# Loads.net
KiCad netlist of a schematic drawn in Altium Designer
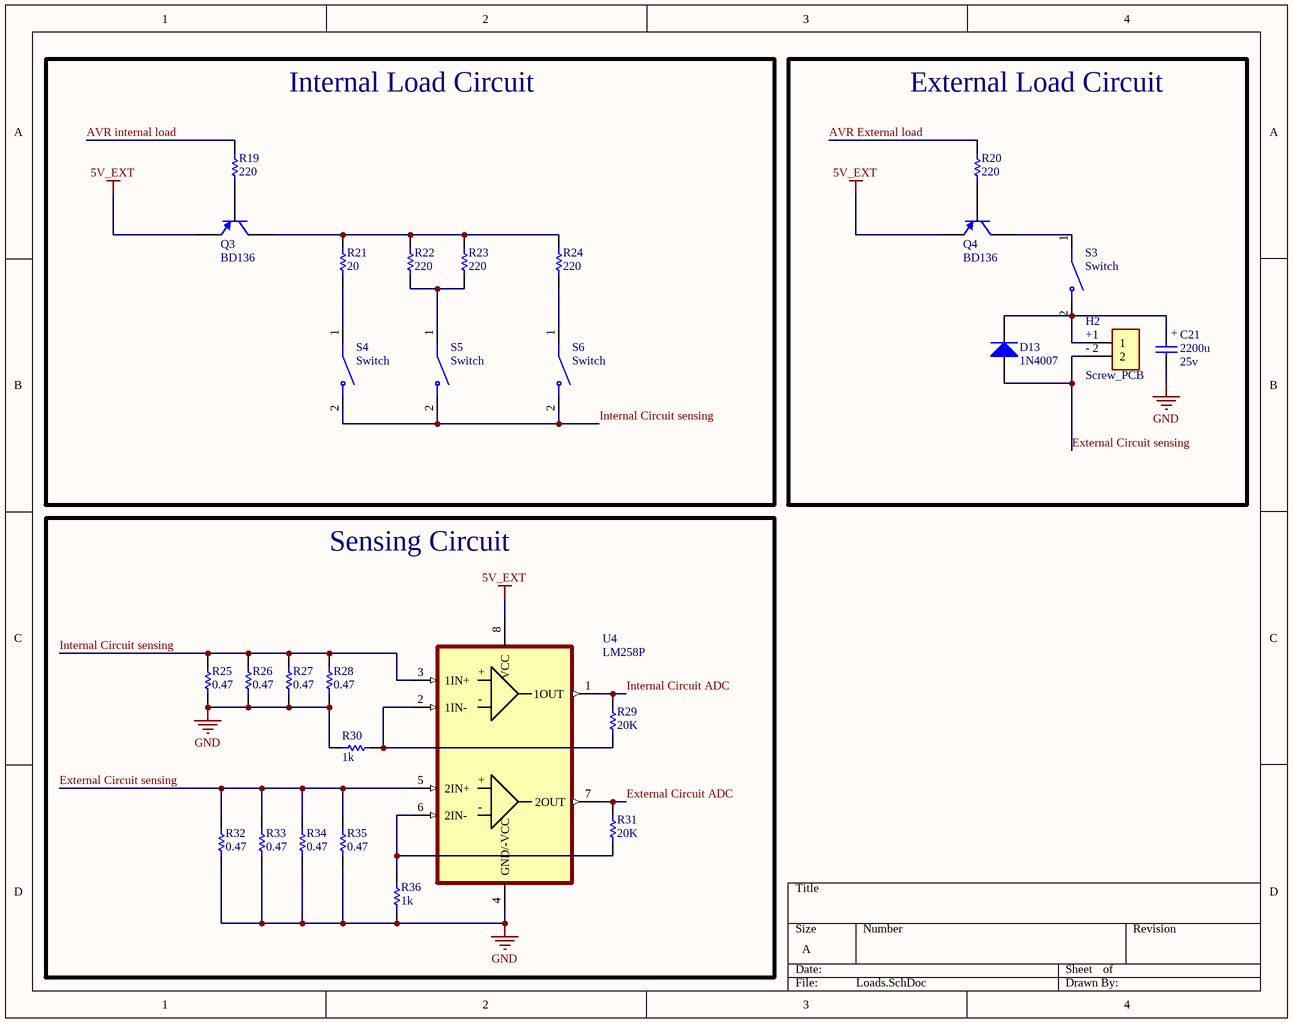
[diagram p0: Loads.SchDoc]

(export (version "E")
  (design (tool "Eeschema 10.0.6"))
  (components
    (comp (ref "C21")
      (value "2200u")
      (footprint "MY_E5-13mm")
      (description "Polar capacitor")
      (fields (field (name "ASID PART NUMBER") "C-AS") (field (name "VOLTE") "25v"))
      (libsource (lib "Mylib+Rev+4") (part "Cap Pol"))
    )
    (comp (ref "D13")
      (value "1N4007")
      (footprint "My_DO41")
      (description "1 Amp Diode")
      (fields (field (name "ASID PART NUMBER") "1n4007-AS"))
      (libsource (lib "Mylib+Rev+4") (part "1N4007"))
    )
    (comp (ref "H2")
      (value "Screw_PCB")
      (footprint "Screw_PCB")
      (description "PCB to screw header")
      (fields (field (name "MF") "TE Connectivity") (field (name "MP") "282837-2"))
      (libsource (lib "Mylib+Rev+4") (part "Screw_PCB"))
    )
    (comp (ref "Q3")
      (value "BD136")
      (footprint "My_TO126")
      (description "Darlington transistor")
      (fields (field (name "ASID PART NUMBER") "BD136-AS"))
      (libsource (lib "Mylib+Rev+4") (part "BD136"))
    )
    (comp (ref "Q4")
      (value "BD136")
      (footprint "My_TO126")
      (description "Darlington transistor")
      (fields (field (name "ASID PART NUMBER") "BD136-AS"))
      (libsource (lib "Mylib+Rev+4") (part "BD136"))
    )
    (comp (ref "R19")
      (value "220")
      (footprint "MY_(0.25w)_0207_10")
      (description "Standard resistor")
      (fields (field (name "ASID PART NUMBER") "Res-AS"))
      (libsource (lib "Mylib+Rev+4") (part "Res"))
    )
    (comp (ref "R20")
      (value "220")
      (footprint "MY_(0.25w)_0207_10")
      (description "Standard resistor")
      (fields (field (name "ASID PART NUMBER") "Res-AS"))
      (libsource (lib "Mylib+Rev+4") (part "Res"))
    )
    (comp (ref "R21")
      (value "20")
      (footprint "MY_(2w)_0617_22")
      (description "Standard resistor")
      (fields (field (name "ASID PART NUMBER") "Res-AS"))
      (libsource (lib "Mylib+Rev+4") (part "Res"))
    )
    (comp (ref "R22")
      (value "220")
      (footprint "MY_(0.25w)_0207_10")
      (description "Standard resistor")
      (fields (field (name "ASID PART NUMBER") "Res-AS"))
      (libsource (lib "Mylib+Rev+4") (part "Res"))
    )
    (comp (ref "R23")
      (value "220")
      (footprint "MY_(0.25w)_0207_10")
      (description "Standard resistor")
      (fields (field (name "ASID PART NUMBER") "Res-AS"))
      (libsource (lib "Mylib+Rev+4") (part "Res"))
    )
    (comp (ref "R24")
      (value "220")
      (footprint "MY_(0.25w)_0207_10")
      (description "Standard resistor")
      (fields (field (name "ASID PART NUMBER") "Res-AS"))
      (libsource (lib "Mylib+Rev+4") (part "Res"))
    )
    (comp (ref "R25")
      (value "0.47")
      (footprint "R0603")
      (description "Standard resistor")
      (fields (field (name "ASID PART NUMBER") "Res-AS"))
      (libsource (lib "Mylib+Rev+4") (part "Res"))
    )
    (comp (ref "R26")
      (value "0.47")
      (footprint "R0603")
      (description "Standard resistor")
      (fields (field (name "ASID PART NUMBER") "Res-AS"))
      (libsource (lib "Mylib+Rev+4") (part "Res"))
    )
    (comp (ref "R27")
      (value "0.47")
      (footprint "R0603")
      (description "Standard resistor")
      (fields (field (name "ASID PART NUMBER") "Res-AS"))
      (libsource (lib "Mylib+Rev+4") (part "Res"))
    )
    (comp (ref "R28")
      (value "0.47")
      (footprint "R0603")
      (description "Standard resistor")
      (fields (field (name "ASID PART NUMBER") "Res-AS"))
      (libsource (lib "Mylib+Rev+4") (part "Res"))
    )
    (comp (ref "R29")
      (value "20K")
      (footprint "R0603")
      (description "Standard resistor")
      (fields (field (name "ASID PART NUMBER") "Res-AS"))
      (libsource (lib "Mylib+Rev+4") (part "Res"))
    )
    (comp (ref "R30")
      (value "1k")
      (footprint "R0603")
      (description "Standard resistor")
      (fields (field (name "ASID PART NUMBER") "Res-AS"))
      (libsource (lib "Mylib+Rev+4") (part "Res"))
    )
    (comp (ref "R31")
      (value "20K")
      (footprint "R0603")
      (description "Standard resistor")
      (fields (field (name "ASID PART NUMBER") "Res-AS"))
      (libsource (lib "Mylib+Rev+4") (part "Res"))
    )
    (comp (ref "R32")
      (value "0.47")
      (footprint "R0603")
      (description "Standard resistor")
      (fields (field (name "ASID PART NUMBER") "Res-AS"))
      (libsource (lib "Mylib+Rev+4") (part "Res"))
    )
    (comp (ref "R33")
      (value "0.47")
      (footprint "R0603")
      (description "Standard resistor")
      (fields (field (name "ASID PART NUMBER") "Res-AS"))
      (libsource (lib "Mylib+Rev+4") (part "Res"))
    )
    (comp (ref "R34")
      (value "0.47")
      (footprint "R0603")
      (description "Standard resistor")
      (fields (field (name "ASID PART NUMBER") "Res-AS"))
      (libsource (lib "Mylib+Rev+4") (part "Res"))
    )
    (comp (ref "R35")
      (value "0.47")
      (footprint "R0603")
      (description "Standard resistor")
      (fields (field (name "ASID PART NUMBER") "Res-AS"))
      (libsource (lib "Mylib+Rev+4") (part "Res"))
    )
    (comp (ref "R36")
      (value "1k")
      (footprint "R0603")
      (description "Standard resistor")
      (fields (field (name "ASID PART NUMBER") "Res-AS"))
      (libsource (lib "Mylib+Rev+4") (part "Res"))
    )
    (comp (ref "S3")
      (value "Switch")
      (footprint "ON/OFF Switch")
      (description "Rocker Switch, RR5 Series, SPST,OFF-ON,Blk Rocker,I/O Legend, 20A, 125VAC, QC")
      (fields (field (name "MP") "RR511D1121") (field (name "MF") "E-Switch"))
      (libsource (lib "Mylib+Rev+4") (part "Switch"))
    )
    (comp (ref "S4")
      (value "Switch")
      (footprint "ON/OFF Switch")
      (description "Rocker Switch, RR5 Series, SPST,OFF-ON,Blk Rocker,I/O Legend, 20A, 125VAC, QC")
      (fields (field (name "MP") "RR511D1121") (field (name "MF") "E-Switch"))
      (libsource (lib "Mylib+Rev+4") (part "Switch"))
    )
    (comp (ref "S5")
      (value "Switch")
      (footprint "ON/OFF Switch")
      (description "Rocker Switch, RR5 Series, SPST,OFF-ON,Blk Rocker,I/O Legend, 20A, 125VAC, QC")
      (fields (field (name "MP") "RR511D1121") (field (name "MF") "E-Switch"))
      (libsource (lib "Mylib+Rev+4") (part "Switch"))
    )
    (comp (ref "S6")
      (value "Switch")
      (footprint "ON/OFF Switch")
      (description "Rocker Switch, RR5 Series, SPST,OFF-ON,Blk Rocker,I/O Legend, 20A, 125VAC, QC")
      (fields (field (name "MP") "RR511D1121") (field (name "MF") "E-Switch"))
      (libsource (lib "Mylib+Rev+4") (part "Switch"))
    )
    (comp (ref "U4")
      (value "LM258P")
      (footprint "DIP 8 LM258")
      (description "Dual standard, industrial-grade, operational amplifier 8-PDIP -25 to 85")
      (fields (field (name "MF") "Texas Instruments"))
      (libsource (lib "Mylib+Rev+4") (part "LM258P"))
    )
  )
  (nets
    (net (code "1") (name "/AVR External load") (class "Default")
      (node (ref "R20") (pin "1") (pinfunction "1_1") (pintype "passive"))
    )
    (net (code "2") (name "/AVR internal load") (class "Default")
      (node (ref "R19") (pin "1") (pinfunction "1_1") (pintype "passive"))
    )
    (net (code "3") (name "/External Circuit ADC") (class "Default")
      (node (ref "R31") (pin "1") (pinfunction "1_1") (pintype "passive"))
      (node (ref "U4") (pin "7") (pinfunction "2OUT_7") (pintype "output"))
    )
    (net (code "4") (name "/External Circuit sensing") (class "Default")
      (node (ref "D13") (pin "A") (pinfunction "A_A") (pintype "passive"))
      (node (ref "H2") (pin "2") (pinfunction "2_2") (pintype "passive"))
      (node (ref "R32") (pin "1") (pinfunction "1_1") (pintype "passive"))
      (node (ref "R33") (pin "1") (pinfunction "1_1") (pintype "passive"))
      (node (ref "R34") (pin "1") (pinfunction "1_1") (pintype "passive"))
      (node (ref "R35") (pin "1") (pinfunction "1_1") (pintype "passive"))
      (node (ref "U4") (pin "5") (pinfunction "2IN+_5") (pintype "input"))
    )
    (net (code "5") (name "/Internal Circuit ADC") (class "Default")
      (node (ref "R29") (pin "1") (pinfunction "1_1") (pintype "passive"))
      (node (ref "U4") (pin "1") (pinfunction "1OUT_1") (pintype "output"))
    )
    (net (code "6") (name "/Internal Circuit sensing") (class "Default")
      (node (ref "R25") (pin "1") (pinfunction "1_1") (pintype "passive"))
      (node (ref "R26") (pin "1") (pinfunction "1_1") (pintype "passive"))
      (node (ref "R27") (pin "1") (pinfunction "1_1") (pintype "passive"))
      (node (ref "R28") (pin "1") (pinfunction "1_1") (pintype "passive"))
      (node (ref "S4") (pin "2") (pinfunction "COM_2") (pintype "passive"))
      (node (ref "S5") (pin "2") (pinfunction "COM_2") (pintype "passive"))
      (node (ref "S6") (pin "2") (pinfunction "COM_2") (pintype "passive"))
      (node (ref "U4") (pin "3") (pinfunction "1IN+_3") (pintype "input"))
    )
    (net (code "7") (name "5V_EXT") (class "Default")
      (node (ref "Q3") (pin "E") (pinfunction "E_E") (pintype "passive"))
      (node (ref "Q4") (pin "E") (pinfunction "E_E") (pintype "passive"))
      (node (ref "U4") (pin "8") (pinfunction "VCC_8") (pintype "power_in"))
    )
    (net (code "8") (name "GND") (class "Default")
      (node (ref "C21") (pin "-") (pinfunction "-_-") (pintype "passive"))
      (node (ref "R25") (pin "2") (pinfunction "2_2") (pintype "passive"))
      (node (ref "R26") (pin "2") (pinfunction "2_2") (pintype "passive"))
      (node (ref "R27") (pin "2") (pinfunction "2_2") (pintype "passive"))
      (node (ref "R28") (pin "2") (pinfunction "2_2") (pintype "passive"))
      (node (ref "R30") (pin "1") (pinfunction "1_1") (pintype "passive"))
      (node (ref "R32") (pin "2") (pinfunction "2_2") (pintype "passive"))
      (node (ref "R33") (pin "2") (pinfunction "2_2") (pintype "passive"))
      (node (ref "R34") (pin "2") (pinfunction "2_2") (pintype "passive"))
      (node (ref "R35") (pin "2") (pinfunction "2_2") (pintype "passive"))
      (node (ref "R36") (pin "2") (pinfunction "2_2") (pintype "passive"))
      (node (ref "U4") (pin "4") (pinfunction "GND/-VCC_4") (pintype "power_in"))
    )
    (net (code "9") (name "Net-(Q3-PadB)") (class "Default")
      (node (ref "Q3") (pin "B") (pinfunction "B_B") (pintype "passive"))
      (node (ref "R19") (pin "2") (pinfunction "2_2") (pintype "passive"))
    )
    (net (code "10") (name "Net-(Q3-PadC)") (class "Default")
      (node (ref "Q3") (pin "C") (pinfunction "C_C") (pintype "passive"))
      (node (ref "R21") (pin "1") (pinfunction "1_1") (pintype "passive"))
      (node (ref "R22") (pin "1") (pinfunction "1_1") (pintype "passive"))
      (node (ref "R23") (pin "1") (pinfunction "1_1") (pintype "passive"))
      (node (ref "R24") (pin "1") (pinfunction "1_1") (pintype "passive"))
    )
    (net (code "11") (name "Net-(Q4-PadB)") (class "Default")
      (node (ref "Q4") (pin "B") (pinfunction "B_B") (pintype "passive"))
      (node (ref "R20") (pin "2") (pinfunction "2_2") (pintype "passive"))
    )
    (net (code "12") (name "Net-(S3-COM)") (class "Default")
      (node (ref "C21") (pin "+") (pinfunction "+_+") (pintype "passive"))
      (node (ref "D13") (pin "K") (pinfunction "K_K") (pintype "passive"))
      (node (ref "H2") (pin "1") (pinfunction "1_1") (pintype "passive"))
      (node (ref "S3") (pin "2") (pinfunction "COM_2") (pintype "passive"))
    )
    (net (code "13") (name "Net-(S3-NO)") (class "Default")
      (node (ref "Q4") (pin "C") (pinfunction "C_C") (pintype "passive"))
      (node (ref "S3") (pin "1") (pinfunction "NO_1") (pintype "passive"))
    )
    (net (code "14") (name "Net-(S4-NO)") (class "Default")
      (node (ref "R21") (pin "2") (pinfunction "2_2") (pintype "passive"))
      (node (ref "S4") (pin "1") (pinfunction "NO_1") (pintype "passive"))
    )
    (net (code "15") (name "Net-(S5-NO)") (class "Default")
      (node (ref "R22") (pin "2") (pinfunction "2_2") (pintype "passive"))
      (node (ref "R23") (pin "2") (pinfunction "2_2") (pintype "passive"))
      (node (ref "S5") (pin "1") (pinfunction "NO_1") (pintype "passive"))
    )
    (net (code "16") (name "Net-(S6-NO)") (class "Default")
      (node (ref "R24") (pin "2") (pinfunction "2_2") (pintype "passive"))
      (node (ref "S6") (pin "1") (pinfunction "NO_1") (pintype "passive"))
    )
    (net (code "17") (name "Net-(U4-1IN-)") (class "Default")
      (node (ref "R29") (pin "2") (pinfunction "2_2") (pintype "passive"))
      (node (ref "R30") (pin "2") (pinfunction "2_2") (pintype "passive"))
      (node (ref "U4") (pin "2") (pinfunction "1IN-_2") (pintype "input"))
    )
    (net (code "18") (name "Net-(U4-2IN-)") (class "Default")
      (node (ref "R31") (pin "2") (pinfunction "2_2") (pintype "passive"))
      (node (ref "R36") (pin "1") (pinfunction "1_1") (pintype "passive"))
      (node (ref "U4") (pin "6") (pinfunction "2IN-_6") (pintype "input"))
    )
  )
)
